# A704X.net
KiCad netlist of a schematic drawn in EAGLE
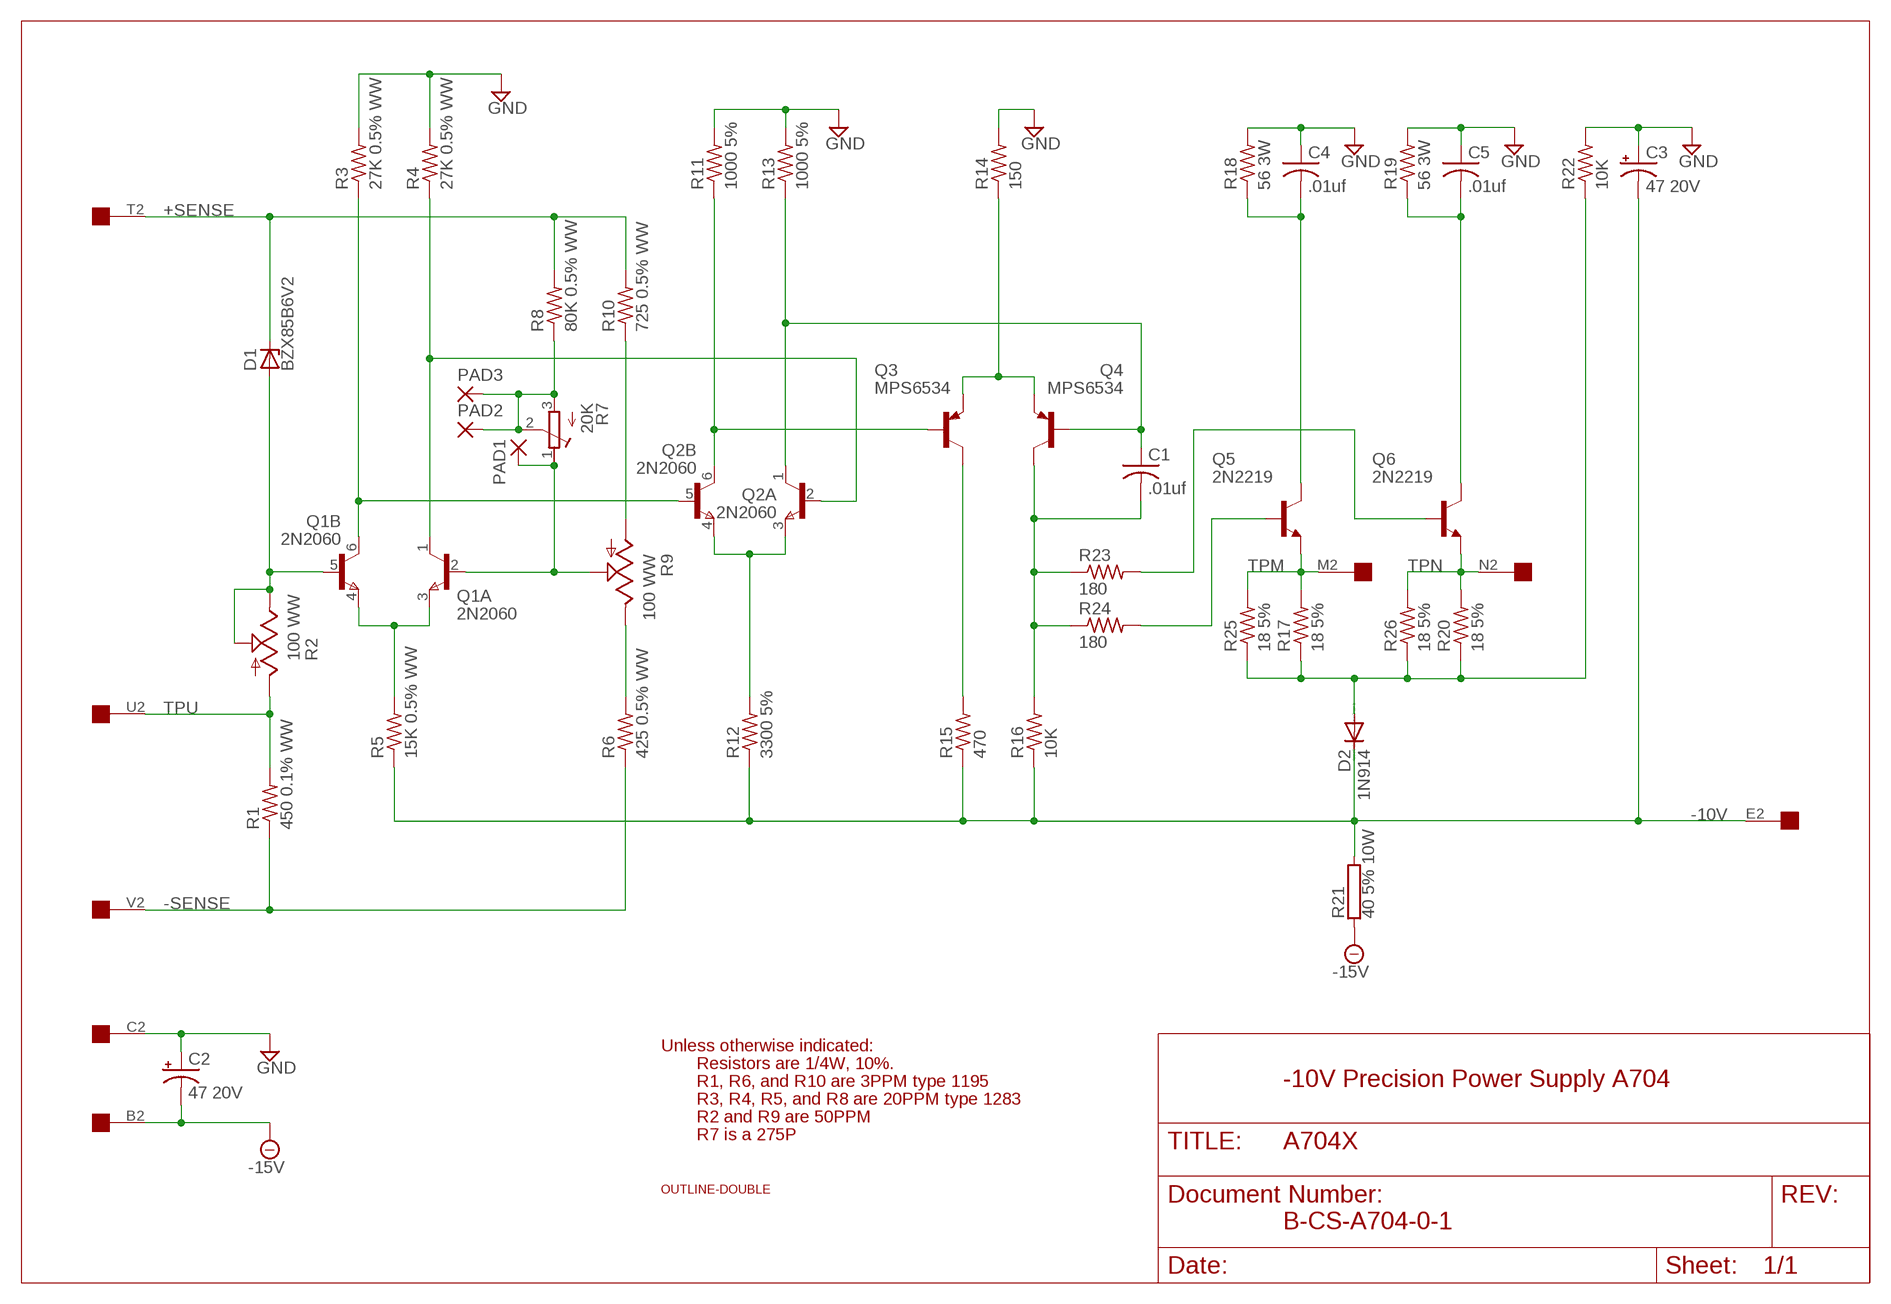
[diagram p0: schematic, sheet 1]

(export (version "E")
  (design (tool "Eeschema 10.0.6"))
  (components
    (comp (ref "C1")
      (value ".01uf")
      (footprint "eagle-import:C050-025X075")
      (libsource (lib "eagle-import") (part "C-US050-025X075"))
    )
    (comp (ref "C2")
      (value "47 20V")
      (footprint "eagle-import:E22-6")
      (libsource (lib "eagle-import") (part "CPOL-USE22-6AXIAL"))
    )
    (comp (ref "C3")
      (value "47 20V")
      (footprint "eagle-import:E22-6")
      (libsource (lib "eagle-import") (part "CPOL-USE22-6AXIAL"))
    )
    (comp (ref "C4")
      (value ".01uf")
      (footprint "eagle-import:C050-025X075")
      (libsource (lib "eagle-import") (part "C-US050-025X075"))
    )
    (comp (ref "C5")
      (value ".01uf")
      (footprint "eagle-import:C050-025X075")
      (libsource (lib "eagle-import") (part "C-US050-025X075"))
    )
    (comp (ref "D1")
      (value "BZX85B6V2")
      (footprint "eagle-import:DO35Z10")
      (libsource (lib "eagle-import") (part "ZENER-DIODEDO35Z10"))
    )
    (comp (ref "D2")
      (value "1N914")
      (footprint "eagle-import:DO35-10")
      (libsource (lib "eagle-import") (part "1N4148DO35-10"))
    )
    (comp (ref "PAD1")
      (value "2,54/1,0")
      (footprint "eagle-import:2,54_1,0")
      (libsource (lib "eagle-import") (part "2,54/1,0"))
    )
    (comp (ref "PAD2")
      (value "2,54/1,0")
      (footprint "eagle-import:2,54_1,0")
      (libsource (lib "eagle-import") (part "2,54/1,0"))
    )
    (comp (ref "PAD3")
      (value "2,54/1,0")
      (footprint "eagle-import:2,54_1,0")
      (libsource (lib "eagle-import") (part "2,54/1,0"))
    )
    (comp (ref "Q1")
      (value "2N2060")
      (footprint "eagle-import:TO78")
      (libsource (lib "eagle-import") (part "MAT-02H"))
    )
    (comp (ref "Q2")
      (value "2N2060")
      (footprint "eagle-import:TO78")
      (libsource (lib "eagle-import") (part "MAT-02H"))
    )
    (comp (ref "Q3")
      (value "MPS6534")
      (footprint "eagle-import:TO39")
      (libsource (lib "eagle-import") (part "2N2904A"))
    )
    (comp (ref "Q4")
      (value "MPS6534")
      (footprint "eagle-import:TO39")
      (libsource (lib "eagle-import") (part "2N2904A"))
    )
    (comp (ref "Q5")
      (value "2N2219")
      (footprint "eagle-import:TO39")
      (libsource (lib "eagle-import") (part "-NPN-TO39-EBC2N1613"))
    )
    (comp (ref "Q6")
      (value "2N2219")
      (footprint "eagle-import:TO39")
      (libsource (lib "eagle-import") (part "-NPN-TO39-EBC2N1613"))
    )
    (comp (ref "R1")
      (value "450 0.1% WW")
      (footprint "eagle-import:P0817_22")
      (libsource (lib "eagle-import") (part "R-US_0817/22"))
    )
    (comp (ref "R2")
      (value "100 WW")
      (footprint "eagle-import:S75P")
      (libsource (lib "eagle-import") (part "TRIM_US-S75P"))
    )
    (comp (ref "R3")
      (value "27K 0.5% WW")
      (footprint "eagle-import:0411_15")
      (libsource (lib "eagle-import") (part "R-US_0411/15"))
    )
    (comp (ref "R4")
      (value "27K 0.5% WW")
      (footprint "eagle-import:0411_15")
      (libsource (lib "eagle-import") (part "R-US_0411/15"))
    )
    (comp (ref "R5")
      (value "15K 0.5% WW")
      (footprint "eagle-import:0411_15")
      (libsource (lib "eagle-import") (part "R-US_0411/15"))
    )
    (comp (ref "R6")
      (value "425 0.5% WW")
      (footprint "eagle-import:P0817_22")
      (libsource (lib "eagle-import") (part "R-US_0817/22"))
    )
    (comp (ref "R7")
      (value "20K")
      (footprint "eagle-import:3006Y")
      (libsource (lib "eagle-import") (part "275P"))
    )
    (comp (ref "R8")
      (value "80K 0.5% WW")
      (footprint "eagle-import:0411_15")
      (libsource (lib "eagle-import") (part "R-US_0411/15"))
    )
    (comp (ref "R9")
      (value "100 WW")
      (footprint "eagle-import:S75P")
      (libsource (lib "eagle-import") (part "TRIM_US-S75P"))
    )
    (comp (ref "R10")
      (value "725 0.5% WW")
      (footprint "eagle-import:P0817_22")
      (libsource (lib "eagle-import") (part "R-US_0817/22"))
    )
    (comp (ref "R11")
      (value "1000 5%")
      (footprint "eagle-import:0207_10")
      (libsource (lib "eagle-import") (part "R-US_0207/10"))
    )
    (comp (ref "R12")
      (value "3300 5%")
      (footprint "eagle-import:0207_10")
      (libsource (lib "eagle-import") (part "R-US_0207/10"))
    )
    (comp (ref "R13")
      (value "1000 5%")
      (footprint "eagle-import:0207_10")
      (libsource (lib "eagle-import") (part "R-US_0207/10"))
    )
    (comp (ref "R14")
      (value "150")
      (footprint "eagle-import:0207_10")
      (libsource (lib "eagle-import") (part "R-US_0207/10"))
    )
    (comp (ref "R15")
      (value "470")
      (footprint "eagle-import:0207_10")
      (libsource (lib "eagle-import") (part "R-US_0207/10"))
    )
    (comp (ref "R16")
      (value "10K")
      (footprint "eagle-import:0207_10")
      (libsource (lib "eagle-import") (part "R-US_0207/10"))
    )
    (comp (ref "R17")
      (value "18 5%")
      (footprint "eagle-import:0207_10")
      (libsource (lib "eagle-import") (part "R-US_0207/10"))
    )
    (comp (ref "R18")
      (value "56 3W")
      (footprint "eagle-import:0411_15")
      (libsource (lib "eagle-import") (part "R-US_0411/15"))
    )
    (comp (ref "R19")
      (value "56 3W")
      (footprint "eagle-import:0411_15")
      (libsource (lib "eagle-import") (part "R-US_0411/15"))
    )
    (comp (ref "R20")
      (value "18 5%")
      (footprint "eagle-import:0207_10")
      (libsource (lib "eagle-import") (part "R-US_0207/10"))
    )
    (comp (ref "R21")
      (value "40 5% 10W")
      (footprint "eagle-import:KH216-8")
      (libsource (lib "eagle-import") (part "RKH216-8"))
    )
    (comp (ref "R22")
      (value "10K")
      (footprint "eagle-import:0207_10")
      (libsource (lib "eagle-import") (part "R-US_0207/10"))
    )
    (comp (ref "R23")
      (value "180")
      (footprint "eagle-import:0207_10")
      (libsource (lib "eagle-import") (part "R-US_0207/10"))
    )
    (comp (ref "R24")
      (value "180")
      (footprint "eagle-import:0207_10")
      (libsource (lib "eagle-import") (part "R-US_0207/10"))
    )
    (comp (ref "R25")
      (value "18 5%")
      (footprint "eagle-import:0207_10")
      (libsource (lib "eagle-import") (part "R-US_0207/10"))
    )
    (comp (ref "R26")
      (value "18 5%")
      (footprint "eagle-import:0207_10")
      (libsource (lib "eagle-import") (part "R-US_0207/10"))
    )
    (comp (ref "U$2")
      (value "OUTLINE-DOUBLE")
      (footprint "eagle-import:DOUBLE")
      (libsource (lib "eagle-import") (part "OUTLINE-DOUBLE"))
    )
    (comp (ref "U$3")
      (value "EDGE-1")
      (footprint "eagle-import:EDGE-CON1")
      (libsource (lib "eagle-import") (part "EDGE-1"))
    )
  )
  (nets
    (net (code "1") (name "-15V") (class "Default")
      (node (ref "C2") (pin "-") (pinfunction "-_-") (pintype "passive"))
      (node (ref "R21") (pin "1") (pinfunction "1_1") (pintype "passive"))
      (node (ref "U$3") (pin "B2") (pinfunction "1_B2") (pintype "bidirectional"))
    )
    (net (code "2") (name "/+SENSE") (class "Default")
      (node (ref "D1") (pin "C") (pinfunction "C_C") (pintype "passive"))
      (node (ref "R10") (pin "2") (pinfunction "2_2") (pintype "passive"))
      (node (ref "R8") (pin "2") (pinfunction "2_2") (pintype "passive"))
      (node (ref "U$3") (pin "T2") (pinfunction "1_T2") (pintype "bidirectional"))
    )
    (net (code "3") (name "/-10V") (class "Default")
      (node (ref "C3") (pin "-") (pinfunction "-_-") (pintype "passive"))
      (node (ref "D2") (pin "C") (pinfunction "C_C") (pintype "passive"))
      (node (ref "R12") (pin "1") (pinfunction "1_1") (pintype "passive"))
      (node (ref "R15") (pin "1") (pinfunction "1_1") (pintype "passive"))
      (node (ref "R16") (pin "1") (pinfunction "1_1") (pintype "passive"))
      (node (ref "R21") (pin "2") (pinfunction "2_2") (pintype "passive"))
      (node (ref "R5") (pin "1") (pinfunction "1_1") (pintype "passive"))
      (node (ref "U$3") (pin "E2") (pinfunction "1_E2") (pintype "bidirectional"))
    )
    (net (code "4") (name "/-SENSE") (class "Default")
      (node (ref "R1") (pin "1") (pinfunction "1_1") (pintype "passive"))
      (node (ref "R6") (pin "1") (pinfunction "1_1") (pintype "passive"))
      (node (ref "U$3") (pin "V2") (pinfunction "1_V2") (pintype "bidirectional"))
    )
    (net (code "5") (name "/TPM") (class "Default")
      (node (ref "Q5") (pin "1") (pinfunction "E_1") (pintype "passive"))
      (node (ref "R17") (pin "2") (pinfunction "2_2") (pintype "passive"))
      (node (ref "R25") (pin "2") (pinfunction "2_2") (pintype "passive"))
      (node (ref "U$3") (pin "M2") (pinfunction "1_M2") (pintype "bidirectional"))
    )
    (net (code "6") (name "/TPN") (class "Default")
      (node (ref "Q6") (pin "1") (pinfunction "E_1") (pintype "passive"))
      (node (ref "R20") (pin "2") (pinfunction "2_2") (pintype "passive"))
      (node (ref "R26") (pin "2") (pinfunction "2_2") (pintype "passive"))
      (node (ref "U$3") (pin "N2") (pinfunction "1_N2") (pintype "bidirectional"))
    )
    (net (code "7") (name "/TPU") (class "Default")
      (node (ref "R1") (pin "2") (pinfunction "2_2") (pintype "passive"))
      (node (ref "R2") (pin "A") (pinfunction "A_A") (pintype "passive"))
      (node (ref "U$3") (pin "U2") (pinfunction "1_U2") (pintype "bidirectional"))
    )
    (net (code "8") (name "GND") (class "Default")
      (node (ref "C2") (pin "+") (pinfunction "+_+") (pintype "passive"))
      (node (ref "C3") (pin "+") (pinfunction "+_+") (pintype "passive"))
      (node (ref "C4") (pin "1") (pinfunction "1_1") (pintype "passive"))
      (node (ref "C5") (pin "1") (pinfunction "1_1") (pintype "passive"))
      (node (ref "R11") (pin "2") (pinfunction "2_2") (pintype "passive"))
      (node (ref "R13") (pin "2") (pinfunction "2_2") (pintype "passive"))
      (node (ref "R14") (pin "2") (pinfunction "2_2") (pintype "passive"))
      (node (ref "R18") (pin "2") (pinfunction "2_2") (pintype "passive"))
      (node (ref "R19") (pin "2") (pinfunction "2_2") (pintype "passive"))
      (node (ref "R22") (pin "2") (pinfunction "2_2") (pintype "passive"))
      (node (ref "R3") (pin "2") (pinfunction "2_2") (pintype "passive"))
      (node (ref "R4") (pin "2") (pinfunction "2_2") (pintype "passive"))
      (node (ref "U$3") (pin "C2") (pinfunction "1_C2") (pintype "bidirectional"))
    )
    (net (code "9") (name "Net-(D2-PadA)") (class "Default")
      (node (ref "D2") (pin "A") (pinfunction "A_A") (pintype "passive"))
      (node (ref "R17") (pin "1") (pinfunction "1_1") (pintype "passive"))
      (node (ref "R20") (pin "1") (pinfunction "1_1") (pintype "passive"))
      (node (ref "R22") (pin "1") (pinfunction "1_1") (pintype "passive"))
      (node (ref "R25") (pin "1") (pinfunction "1_1") (pintype "passive"))
      (node (ref "R26") (pin "1") (pinfunction "1_1") (pintype "passive"))
    )
    (net (code "10") (name "Net-(PAD1-P)") (class "Default")
      (node (ref "PAD1") (pin "1") (pinfunction "P_1") (pintype "passive"))
      (node (ref "Q1") (pin "2") (pinfunction "B_2") (pintype "passive"))
      (node (ref "R7") (pin "1") (pinfunction "A_1") (pintype "passive"))
      (node (ref "R9") (pin "S") (pinfunction "S_S") (pintype "passive"))
    )
    (net (code "11") (name "Net-(PAD2-P)") (class "Default")
      (node (ref "PAD2") (pin "1") (pinfunction "P_1") (pintype "passive"))
      (node (ref "PAD3") (pin "1") (pinfunction "P_1") (pintype "passive"))
      (node (ref "R7") (pin "2") (pinfunction "S_2") (pintype "passive"))
      (node (ref "R7") (pin "3") (pinfunction "E_3") (pintype "passive"))
      (node (ref "R8") (pin "1") (pinfunction "1_1") (pintype "passive"))
    )
    (net (code "12") (name "Net-(Q1A-C)") (class "Default")
      (node (ref "Q1") (pin "1") (pinfunction "C_1") (pintype "passive"))
      (node (ref "Q2") (pin "2") (pinfunction "B_2") (pintype "passive"))
      (node (ref "R4") (pin "1") (pinfunction "1_1") (pintype "passive"))
    )
    (net (code "13") (name "Net-(Q1A-E)") (class "Default")
      (node (ref "Q1") (pin "3") (pinfunction "E_3") (pintype "passive"))
      (node (ref "Q1") (pin "4") (pinfunction "E_4") (pintype "passive"))
      (node (ref "R5") (pin "2") (pinfunction "2_2") (pintype "passive"))
    )
    (net (code "14") (name "Net-(Q1B-B)") (class "Default")
      (node (ref "D1") (pin "A") (pinfunction "A_A") (pintype "passive"))
      (node (ref "Q1") (pin "5") (pinfunction "B_5") (pintype "passive"))
      (node (ref "R2") (pin "E") (pinfunction "E_E") (pintype "passive"))
      (node (ref "R2") (pin "S") (pinfunction "S_S") (pintype "passive"))
    )
    (net (code "15") (name "Net-(Q1B-C)") (class "Default")
      (node (ref "Q1") (pin "6") (pinfunction "C_6") (pintype "passive"))
      (node (ref "Q2") (pin "5") (pinfunction "B_5") (pintype "passive"))
      (node (ref "R3") (pin "1") (pinfunction "1_1") (pintype "passive"))
    )
    (net (code "16") (name "Net-(Q2A-C)") (class "Default")
      (node (ref "C1") (pin "1") (pinfunction "1_1") (pintype "passive"))
      (node (ref "Q2") (pin "1") (pinfunction "C_1") (pintype "passive"))
      (node (ref "Q4") (pin "2") (pinfunction "B_2") (pintype "passive"))
      (node (ref "R13") (pin "1") (pinfunction "1_1") (pintype "passive"))
    )
    (net (code "17") (name "Net-(Q2A-E)") (class "Default")
      (node (ref "Q2") (pin "3") (pinfunction "E_3") (pintype "passive"))
      (node (ref "Q2") (pin "4") (pinfunction "E_4") (pintype "passive"))
      (node (ref "R12") (pin "2") (pinfunction "2_2") (pintype "passive"))
    )
    (net (code "18") (name "Net-(Q2B-C)") (class "Default")
      (node (ref "Q2") (pin "6") (pinfunction "C_6") (pintype "passive"))
      (node (ref "Q3") (pin "2") (pinfunction "B_2") (pintype "passive"))
      (node (ref "R11") (pin "1") (pinfunction "1_1") (pintype "passive"))
    )
    (net (code "19") (name "Net-(Q3-C)") (class "Default")
      (node (ref "Q3") (pin "3") (pinfunction "C_3") (pintype "passive"))
      (node (ref "R15") (pin "2") (pinfunction "2_2") (pintype "passive"))
    )
    (net (code "20") (name "Net-(Q3-E)") (class "Default")
      (node (ref "Q3") (pin "1") (pinfunction "E_1") (pintype "passive"))
      (node (ref "Q4") (pin "1") (pinfunction "E_1") (pintype "passive"))
      (node (ref "R14") (pin "1") (pinfunction "1_1") (pintype "passive"))
    )
    (net (code "21") (name "Net-(Q4-C)") (class "Default")
      (node (ref "C1") (pin "2") (pinfunction "2_2") (pintype "passive"))
      (node (ref "Q4") (pin "3") (pinfunction "C_3") (pintype "passive"))
      (node (ref "R16") (pin "2") (pinfunction "2_2") (pintype "passive"))
      (node (ref "R23") (pin "1") (pinfunction "1_1") (pintype "passive"))
      (node (ref "R24") (pin "1") (pinfunction "1_1") (pintype "passive"))
    )
    (net (code "22") (name "Net-(Q5-B)") (class "Default")
      (node (ref "Q5") (pin "2") (pinfunction "B_2") (pintype "passive"))
      (node (ref "R24") (pin "2") (pinfunction "2_2") (pintype "passive"))
    )
    (net (code "23") (name "Net-(Q5-C)") (class "Default")
      (node (ref "C4") (pin "2") (pinfunction "2_2") (pintype "passive"))
      (node (ref "Q5") (pin "3") (pinfunction "C_3") (pintype "passive"))
      (node (ref "R18") (pin "1") (pinfunction "1_1") (pintype "passive"))
    )
    (net (code "24") (name "Net-(Q6-B)") (class "Default")
      (node (ref "Q6") (pin "2") (pinfunction "B_2") (pintype "passive"))
      (node (ref "R23") (pin "2") (pinfunction "2_2") (pintype "passive"))
    )
    (net (code "25") (name "Net-(Q6-C)") (class "Default")
      (node (ref "C5") (pin "2") (pinfunction "2_2") (pintype "passive"))
      (node (ref "Q6") (pin "3") (pinfunction "C_3") (pintype "passive"))
      (node (ref "R19") (pin "1") (pinfunction "1_1") (pintype "passive"))
    )
    (net (code "26") (name "Net-(R6-Pad2)") (class "Default")
      (node (ref "R6") (pin "2") (pinfunction "2_2") (pintype "passive"))
      (node (ref "R9") (pin "E") (pinfunction "E_E") (pintype "passive"))
    )
    (net (code "27") (name "Net-(R10-Pad1)") (class "Default")
      (node (ref "R10") (pin "1") (pinfunction "1_1") (pintype "passive"))
      (node (ref "R9") (pin "A") (pinfunction "A_A") (pintype "passive"))
    )
  )
)
